# pmu_2.net
KiCad netlist of a schematic drawn in Altium Designer
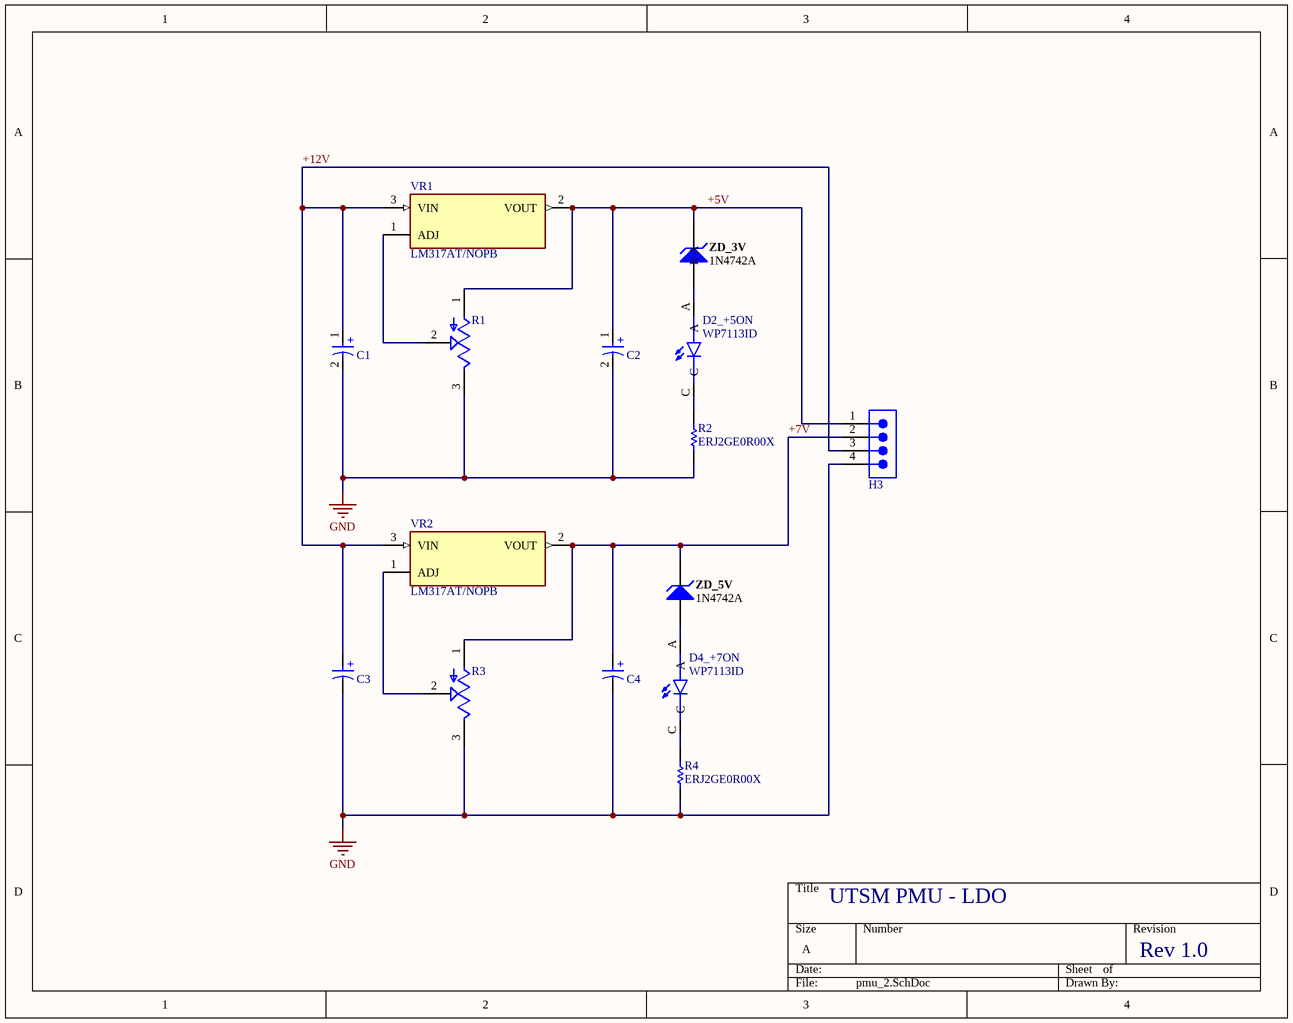
[diagram p0: pmu_2.SchDoc]

(export (version "E")
  (design (tool "Eeschema 10.0.6"))
  (components
    (comp (ref "C1")
      (value "2.2µF")
      (footprint "pmu:WCAP-ATG5_D5H11")
      (description "WCAP-ATG5 Aluminum Electrolytic Capacitor, Radial, THT, D5 x H11mm, 2.2µF, 50V")
      (fields
        (field (name "MANUFACTURER PART NUMBER") "860020672006")
        (field (name "MANUFACTURER") "Wurth Elektronik")
      )
      (libsource (lib "1ufcap-Altium_WCAP-ATG5_rev22d") (part "860020672006"))
    )
    (comp (ref "C2")
      (value "1.1uF")
      (footprint "pmu:WCAP-ATG5_D5H11")
      (description "WCAP-ATG5 Aluminum Electrolytic Capacitor, Radial, THT, D5 x H11mm, 2.2µF, 50V")
      (fields
        (field (name "MANUFACTURER PART NUMBER") "860020672006")
        (field (name "MANUFACTURER") "Wurth Elektronik")
      )
      (libsource (lib "1ufcap-Altium_WCAP-ATG5_rev22d") (part "860020672006"))
    )
    (comp (ref "C3")
      (value "2.2µF")
      (footprint "WCAP-ATG5_D5H11")
      (description "WCAP-ATG5 Aluminum Electrolytic Capacitor, Radial, THT, D5 x H11mm, 2.2µF, 50V")
      (fields
        (field (name "MANUFACTURER PART NUMBER") "860020672006")
        (field (name "MANUFACTURER") "Wurth Elektronik")
      )
      (libsource (lib "") (part "860020672006_1"))
    )
    (comp (ref "C4")
      (value "1.1uF")
      (footprint "pmu:WCAP-ATG5_D5H11")
      (description "WCAP-ATG5 Aluminum Electrolytic Capacitor, Radial, THT, D5 x H11mm, 2.2µF, 50V")
      (fields
        (field (name "MANUFACTURER PART NUMBER") "860020672006")
        (field (name "MANUFACTURER") "Wurth Elektronik")
      )
      (libsource (lib "") (part "860020672006_1"))
    )
    (comp (ref "D2_+5ON")
      (value "WP7113ID")
      (footprint "pmu:LED_WP7113ID")
      (description "Red 617nm LED Indication - Discrete 2V Radial")
      (fields (field (name "MF") "Kingbright"))
      (libsource (lib "leds-WP7113ID") (part "WP7113ID"))
    )
    (comp (ref "D4_+7ON")
      (value "WP7113ID")
      (footprint "pmu:LED_WP7113ID")
      (description "Red 617nm LED Indication - Discrete 2V Radial")
      (fields (field (name "MF") "Kingbright"))
      (libsource (lib "leds-WP7113ID") (part "WP7113ID"))
    )
    (comp (ref "H3")
      (value "61300411121")
      (footprint "61300411121")
      (description "WR-PHD Pin Header, THT, Vertical, pitch 2.54mm, 1 Row, 4P")
      (fields (field (name "MANUFACTURER") "Wurth Elektronik"))
      (libsource (lib "pmu") (part "61300411121"))
    )
    (comp (ref "R1")
      (value "~")
      (footprint "TRIM_3362P-1-103LF")
      (description "10 kOhms 0.5W, 1/2W PC Pins Through Hole Trimmer Potentiometer Cermet 1 Turn Top Adjustment")
      (fields (field (name "DIGI-KEY_PART_NUMBER") "3362P-103LF-ND") (field (name "MF") "Bourns"))
      (libsource (lib "*") (part "3362P-1-103LF"))
    )
    (comp (ref "R2")
      (value "ERJ2GE0R00X")
      (footprint "RESC1005X40X25LL05T05")
      (description "Chip Resistor, 0 Ohm, 0.1 W, -55 to 155 degC, 0402 (1005 Metric), RoHS, Tape and Reel")
      (fields (field (name "MANUFACTURER") "Panasonic") (field (name "TOLERANCE") "5%"))
      (libsource (lib "Altium Content Vault") (part "RES-2"))
    )
    (comp (ref "R3")
      (value "~")
      (footprint "TRIM_3362P-1-103LF")
      (description "10 kOhms 0.5W, 1/2W PC Pins Through Hole Trimmer Potentiometer Cermet 1 Turn Top Adjustment")
      (fields (field (name "DIGI-KEY_PART_NUMBER") "3362P-103LF-ND") (field (name "MF") "Bourns"))
      (libsource (lib "*") (part "3362P-1-103LF"))
    )
    (comp (ref "R4")
      (value "ERJ2GE0R00X")
      (footprint "RESC1005X40X25LL05T05")
      (description "Chip Resistor, 0 Ohm, 0.1 W, -55 to 155 degC, 0402 (1005 Metric), RoHS, Tape and Reel")
      (fields (field (name "MANUFACTURER") "Panasonic") (field (name "TOLERANCE") "5%"))
      (libsource (lib "Altium Content Vault") (part "RES-2"))
    )
    (comp (ref "VR1")
      (value "LM317AT/NOPB")
      (footprint "pmu:TO254P1054X470X1955-3")
      (libsource (lib "vreg-LM317AT_NOPB") (part "LM317AT/NOPB"))
    )
    (comp (ref "VR2")
      (value "LM317AT/NOPB")
      (footprint "pmu:TO254P1054X470X1955-3")
      (libsource (lib "vreg-LM317AT_NOPB") (part "LM317AT/NOPB"))
    )
    (comp (ref "ZD_3V")
      (value "1N4742A")
      (footprint "FAIR-DO-41-2_V")
      (description "Zener Diode, 12V, 1W, 5%, -65 to 200 degC, 2-Pin DO-41, Body 2.72 x 5.2 mm, RoHS")
      (fields (field (name "TOLERANCE") "5%") (field (name "MANUFACTURER") "Fairchild Semiconductor"))
      (libsource (lib "") (part "FAIR-DZEN-A1K2-2_1"))
    )
    (comp (ref "ZD_5V")
      (value "1N4742A")
      (footprint "FAIR-DO-41-2_V")
      (description "Zener Diode, 12V, 1W, 5%, -65 to 200 degC, 2-Pin DO-41, Body 2.72 x 5.2 mm, RoHS")
      (fields (field (name "TOLERANCE") "5%") (field (name "MANUFACTURER") "Fairchild Semiconductor"))
      (libsource (lib "Altium Content Vault") (part "FAIR-DZEN-A1K2-2"))
    )
  )
  (nets
    (net (code "1") (name "/+5V") (class "Default")
      (node (ref "C2") (pin "1") (pinfunction "P_1") (pintype "passive"))
      (node (ref "H3") (pin "1") (pinfunction "1_1") (pintype "passive"))
      (node (ref "R1") (pin "1") (pinfunction "CCW_1") (pintype "passive"))
      (node (ref "VR1") (pin "2") (pinfunction "VOUT_2") (pintype "output"))
      (node (ref "ZD_3V") (pin "2") (pinfunction "K_2") (pintype "passive"))
    )
    (net (code "2") (name "/+7V") (class "Default")
      (node (ref "C4") (pin "1") (pinfunction "P_1") (pintype "passive"))
      (node (ref "H3") (pin "2") (pinfunction "2_2") (pintype "passive"))
      (node (ref "R3") (pin "1") (pinfunction "CCW_1") (pintype "passive"))
      (node (ref "VR2") (pin "2") (pinfunction "VOUT_2") (pintype "output"))
      (node (ref "ZD_5V") (pin "2") (pinfunction "K_2") (pintype "passive"))
    )
    (net (code "3") (name "/+12V") (class "Default")
      (node (ref "C1") (pin "1") (pinfunction "P_1") (pintype "passive"))
      (node (ref "C3") (pin "1") (pinfunction "P_1") (pintype "passive"))
      (node (ref "H3") (pin "3") (pinfunction "3_3") (pintype "passive"))
      (node (ref "VR1") (pin "3") (pinfunction "VIN_3") (pintype "input"))
      (node (ref "VR2") (pin "3") (pinfunction "VIN_3") (pintype "input"))
    )
    (net (code "4") (name "GND") (class "Default")
      (node (ref "C1") (pin "2") (pinfunction "N_2") (pintype "passive"))
      (node (ref "C2") (pin "2") (pinfunction "N_2") (pintype "passive"))
      (node (ref "C3") (pin "2") (pinfunction "N_2") (pintype "passive"))
      (node (ref "C4") (pin "2") (pinfunction "N_2") (pintype "passive"))
      (node (ref "H3") (pin "4") (pinfunction "4_4") (pintype "passive"))
      (node (ref "R1") (pin "3") (pinfunction "CW_3") (pintype "passive"))
      (node (ref "R2") (pin "1") (pinfunction "1_1") (pintype "passive"))
      (node (ref "R3") (pin "3") (pinfunction "CW_3") (pintype "passive"))
      (node (ref "R4") (pin "1") (pinfunction "1_1") (pintype "passive"))
    )
    (net (code "5") (name "Net-(D2_+5ON-PadC)") (class "Default")
      (node (ref "D2_+5ON") (pin "C") (pinfunction "C_C") (pintype "passive"))
      (node (ref "R2") (pin "2") (pinfunction "2_2") (pintype "passive"))
    )
    (net (code "6") (name "Net-(D4_+7ON-PadC)") (class "Default")
      (node (ref "D4_+7ON") (pin "C") (pinfunction "C_C") (pintype "passive"))
      (node (ref "R4") (pin "2") (pinfunction "2_2") (pintype "passive"))
    )
    (net (code "7") (name "Net-(R1-WIPER)") (class "Default")
      (node (ref "R1") (pin "2") (pinfunction "WIPER_2") (pintype "passive"))
      (node (ref "VR1") (pin "1") (pinfunction "ADJ_1") (pintype "passive"))
    )
    (net (code "8") (name "Net-(R3-WIPER)") (class "Default")
      (node (ref "R3") (pin "2") (pinfunction "WIPER_2") (pintype "passive"))
      (node (ref "VR2") (pin "1") (pinfunction "ADJ_1") (pintype "passive"))
    )
    (net (code "9") (name "Net-(ZD_3V-A)") (class "Default")
      (node (ref "D2_+5ON") (pin "A") (pinfunction "A_A") (pintype "passive"))
      (node (ref "ZD_3V") (pin "1") (pinfunction "A_1") (pintype "passive"))
    )
    (net (code "10") (name "Net-(ZD_5V-A)") (class "Default")
      (node (ref "D4_+7ON") (pin "A") (pinfunction "A_A") (pintype "passive"))
      (node (ref "ZD_5V") (pin "1") (pinfunction "A_1") (pintype "passive"))
    )
  )
)
